# SMAC-2530.net
KiCad netlist of a schematic drawn in EAGLE
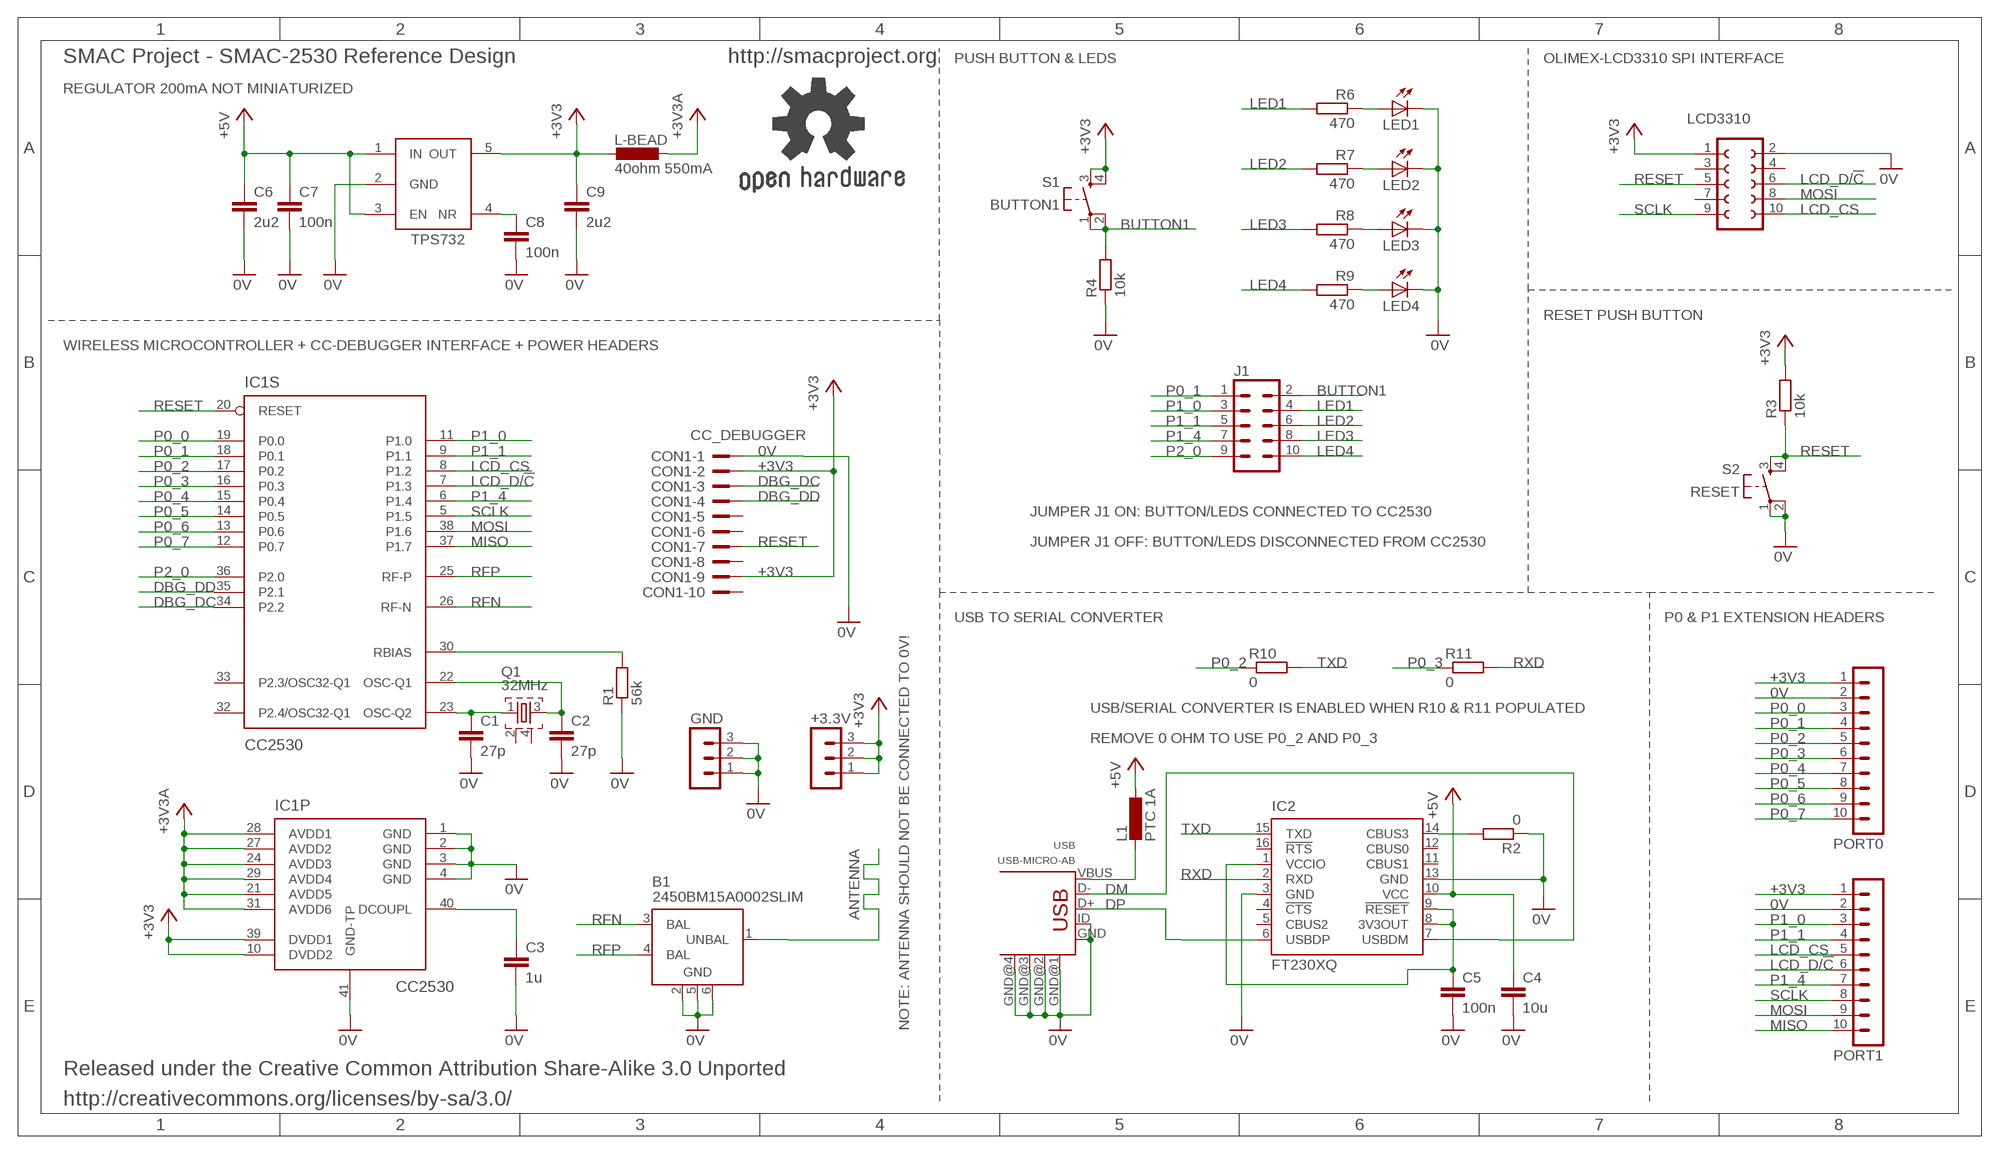
[diagram p0: schematic, sheet 1]

(export (version "E")
  (design (tool "Eeschema 10.0.6"))
  (components
    (comp (ref "+3.3V")
      (value "MA03-1")
      (footprint "eagle-import:MA03-1")
      (libsource (lib "eagle-import") (part "MA03-1"))
    )
    (comp (ref "B1")
      (value "2450BM15A0002SLIM")
      (footprint "eagle-import:2450BM15A0002-SLIM")
      (libsource (lib "eagle-import") (part "2450BM15A0002SLIM"))
    )
    (comp (ref "C1")
      (value "27p")
      (footprint "eagle-import:C0603K")
      (libsource (lib "eagle-import") (part "C-EUC0603K"))
    )
    (comp (ref "C2")
      (value "27p")
      (footprint "eagle-import:C0603K")
      (libsource (lib "eagle-import") (part "C-EUC0603K"))
    )
    (comp (ref "C3")
      (value "1u")
      (footprint "eagle-import:C0603K")
      (libsource (lib "eagle-import") (part "C-EUC0603K"))
    )
    (comp (ref "C4")
      (value "10u")
      (footprint "eagle-import:C0603K")
      (libsource (lib "eagle-import") (part "C-EUC0603K"))
    )
    (comp (ref "C5")
      (value "100n")
      (footprint "eagle-import:C0603K")
      (libsource (lib "eagle-import") (part "C-EUC0603K"))
    )
    (comp (ref "C6")
      (value "2u2")
      (footprint "eagle-import:C0603K")
      (libsource (lib "eagle-import") (part "C-EUC0603K"))
    )
    (comp (ref "C7")
      (value "100n")
      (footprint "eagle-import:C0603K")
      (libsource (lib "eagle-import") (part "C-EUC0603K"))
    )
    (comp (ref "C8")
      (value "100n")
      (footprint "eagle-import:C0603K")
      (libsource (lib "eagle-import") (part "C-EUC0603K"))
    )
    (comp (ref "C9")
      (value "2u2")
      (footprint "eagle-import:C0603K")
      (libsource (lib "eagle-import") (part "C-EUC0603K"))
    )
    (comp (ref "CON1")
      (value "CC_DEBUGGER")
      (footprint "eagle-import:PAK100_2500-10")
      (fields (field (name "MF") "3M") (field (name "MPN") "2510-6002UB"))
      (libsource (lib "eagle-import") (part "2510-"))
    )
    (comp (ref "GND")
      (value "MA03-1")
      (footprint "eagle-import:MA03-1")
      (libsource (lib "eagle-import") (part "MA03-1"))
    )
    (comp (ref "GOLD_ORB_SM1")
      (value "OSHWLOGO_GOLD_ORB_SM")
      (footprint "eagle-import:OSHW2")
      (libsource (lib "eagle-import") (part "OSHWLOGO_GOLD_ORB_SM"))
    )
    (comp (ref "IC1")
      (value "CC2530")
      (footprint "eagle-import:QFN50P600X600X100-41N")
      (libsource (lib "eagle-import") (part "CC2530"))
    )
    (comp (ref "IC2")
      (value "FT230XQ")
      (footprint "eagle-import:QFN16")
      (libsource (lib "eagle-import") (part "FT230XQ"))
    )
    (comp (ref "IC3")
      (value "TPS732XX")
      (footprint "eagle-import:SOT23")
      (libsource (lib "eagle-import") (part "TPS732XX"))
    )
    (comp (ref "J1")
      (value "MA05-2")
      (footprint "eagle-import:MA05-2")
      (libsource (lib "eagle-import") (part "MA05-2"))
    )
    (comp (ref "L-BEAD")
      (value "40ohm 550mA")
      (footprint "eagle-import:L0603K")
      (libsource (lib "eagle-import") (part "L-EUL0603K"))
    )
    (comp (ref "L1")
      (value "PTC 1A")
      (footprint "eagle-import:L0603K")
      (libsource (lib "eagle-import") (part "L-EUL0603K"))
    )
    (comp (ref "LCD3310")
      (value "FE05-2")
      (footprint "eagle-import:FE05-2")
      (libsource (lib "eagle-import") (part "FE05-2"))
    )
    (comp (ref "LED1")
      (value "LEDCHIP-LED0805")
      (footprint "eagle-import:CHIP-LED0805")
      (libsource (lib "eagle-import") (part "LEDCHIP-LED0805"))
    )
    (comp (ref "LED2")
      (value "LEDCHIP-LED0805")
      (footprint "eagle-import:CHIP-LED0805")
      (libsource (lib "eagle-import") (part "LEDCHIP-LED0805"))
    )
    (comp (ref "LED3")
      (value "LEDCHIP-LED0805")
      (footprint "eagle-import:CHIP-LED0805")
      (libsource (lib "eagle-import") (part "LEDCHIP-LED0805"))
    )
    (comp (ref "LED4")
      (value "LEDCHIP-LED0805")
      (footprint "eagle-import:CHIP-LED0805")
      (libsource (lib "eagle-import") (part "LEDCHIP-LED0805"))
    )
    (comp (ref "PORT0")
      (value "MA10-1")
      (footprint "eagle-import:MA10-1")
      (libsource (lib "eagle-import") (part "MA10-1"))
    )
    (comp (ref "PORT1")
      (value "MA10-1")
      (footprint "eagle-import:MA10-1")
      (libsource (lib "eagle-import") (part "MA10-1"))
    )
    (comp (ref "Q1")
      (value "32MHz")
      (footprint "eagle-import:FA-128")
      (libsource (lib "eagle-import") (part "FA-128"))
    )
    (comp (ref "R1")
      (value "56k")
      (footprint "eagle-import:R0603K")
      (libsource (lib "eagle-import") (part "R-EU_R0603K"))
    )
    (comp (ref "R2")
      (value "0")
      (footprint "eagle-import:R0603K")
      (libsource (lib "eagle-import") (part "R-EU_R0603K"))
    )
    (comp (ref "R3")
      (value "10k")
      (footprint "eagle-import:R0603K")
      (libsource (lib "eagle-import") (part "R-EU_R0603K"))
    )
    (comp (ref "R4")
      (value "10k")
      (footprint "eagle-import:R0603K")
      (libsource (lib "eagle-import") (part "R-EU_R0603K"))
    )
    (comp (ref "R6")
      (value "470")
      (footprint "eagle-import:R0603K")
      (libsource (lib "eagle-import") (part "R-EU_R0603K"))
    )
    (comp (ref "R7")
      (value "470")
      (footprint "eagle-import:R0603K")
      (libsource (lib "eagle-import") (part "R-EU_R0603K"))
    )
    (comp (ref "R8")
      (value "470")
      (footprint "eagle-import:R0603K")
      (libsource (lib "eagle-import") (part "R-EU_R0603K"))
    )
    (comp (ref "R9")
      (value "470")
      (footprint "eagle-import:R0603K")
      (libsource (lib "eagle-import") (part "R-EU_R0603K"))
    )
    (comp (ref "R10")
      (value "0")
      (footprint "eagle-import:R0603K")
      (libsource (lib "eagle-import") (part "R-EU_R0603K"))
    )
    (comp (ref "R11")
      (value "0")
      (footprint "eagle-import:R0603K")
      (libsource (lib "eagle-import") (part "R-EU_R0603K"))
    )
    (comp (ref "S1")
      (value "BUTTON1")
      (footprint "eagle-import:ALCOSWITCH-SMD")
      (libsource (lib "eagle-import") (part "ALCOSWITCH-SMD"))
    )
    (comp (ref "S2")
      (value "RESET")
      (footprint "eagle-import:ALCOSWITCH-SMD")
      (libsource (lib "eagle-import") (part "ALCOSWITCH-SMD"))
    )
    (comp (ref "USB")
      (value "USB-MICRO-AB")
      (footprint "eagle-import:USB-UAB-S1")
      (libsource (lib "eagle-import") (part "USB-OTG_SHIELD"))
    )
  )
  (nets
    (net (code "1") (name "+3V3") (class "Default")
      (node (ref "+3.3V") (pin "1") (pinfunction "1_1") (pintype "passive"))
      (node (ref "+3.3V") (pin "2") (pinfunction "2_2") (pintype "passive"))
      (node (ref "+3.3V") (pin "3") (pinfunction "3_3") (pintype "passive"))
      (node (ref "C9") (pin "1") (pinfunction "1_1") (pintype "passive"))
      (node (ref "CON1") (pin "2") (pinfunction "KL_2") (pintype "passive"))
      (node (ref "CON1") (pin "9") (pinfunction "KL_9") (pintype "passive"))
      (node (ref "IC1") (pin "10") (pinfunction "DVDD2_10") (pintype "power_in"))
      (node (ref "IC1") (pin "39") (pinfunction "DVDD1_39") (pintype "power_in"))
      (node (ref "IC3") (pin "5") (pinfunction "OUT_5") (pintype "bidirectional"))
      (node (ref "L-BEAD") (pin "1") (pinfunction "1_1") (pintype "passive"))
      (node (ref "LCD3310") (pin "1") (pinfunction "1_1") (pintype "passive"))
      (node (ref "PORT0") (pin "1") (pinfunction "1_1") (pintype "passive"))
      (node (ref "PORT1") (pin "1") (pinfunction "1_1") (pintype "passive"))
      (node (ref "R3") (pin "2") (pinfunction "2_2") (pintype "passive"))
      (node (ref "S1") (pin "3") (pinfunction "S_3") (pintype "passive"))
      (node (ref "S1") (pin "4") (pinfunction "S1_4") (pintype "passive"))
    )
    (net (code "2") (name "+3V3A") (class "Default")
      (node (ref "IC1") (pin "21") (pinfunction "AVDD5_21") (pintype "power_in"))
      (node (ref "IC1") (pin "24") (pinfunction "AVDD3_24") (pintype "power_in"))
      (node (ref "IC1") (pin "27") (pinfunction "AVDD2_27") (pintype "power_in"))
      (node (ref "IC1") (pin "28") (pinfunction "AVDD1_28") (pintype "power_in"))
      (node (ref "IC1") (pin "29") (pinfunction "AVDD4_29") (pintype "power_in"))
      (node (ref "IC1") (pin "31") (pinfunction "AVDD6_31") (pintype "power_in"))
      (node (ref "L-BEAD") (pin "2") (pinfunction "2_2") (pintype "passive"))
    )
    (net (code "3") (name "+5V") (class "Default")
      (node (ref "C4") (pin "1") (pinfunction "1_1") (pintype "passive"))
      (node (ref "C6") (pin "1") (pinfunction "1_1") (pintype "passive"))
      (node (ref "C7") (pin "1") (pinfunction "1_1") (pintype "passive"))
      (node (ref "IC2") (pin "10") (pinfunction "VCC_10") (pintype "power_in"))
      (node (ref "IC3") (pin "1") (pinfunction "IN_1") (pintype "bidirectional"))
      (node (ref "IC3") (pin "3") (pinfunction "EN_3") (pintype "bidirectional"))
      (node (ref "L1") (pin "1") (pinfunction "1_1") (pintype "passive"))
    )
    (net (code "4") (name "/BUTTON1") (class "Default")
      (node (ref "J1") (pin "2") (pinfunction "2_2") (pintype "passive"))
      (node (ref "R4") (pin "2") (pinfunction "2_2") (pintype "passive"))
      (node (ref "S1") (pin "1") (pinfunction "P_1") (pintype "passive"))
      (node (ref "S1") (pin "2") (pinfunction "P1_2") (pintype "passive"))
    )
    (net (code "5") (name "/DBG_DC") (class "Default")
      (node (ref "CON1") (pin "3") (pinfunction "KL_3") (pintype "passive"))
      (node (ref "IC1") (pin "34") (pinfunction "P2.2_34") (pintype "bidirectional"))
    )
    (net (code "6") (name "/DBG_DD") (class "Default")
      (node (ref "CON1") (pin "4") (pinfunction "KL_4") (pintype "passive"))
      (node (ref "IC1") (pin "35") (pinfunction "P2.1_35") (pintype "bidirectional"))
    )
    (net (code "7") (name "/DM") (class "Default")
      (node (ref "IC2") (pin "7") (pinfunction "USBDM_7") (pintype "input"))
      (node (ref "USB") (pin "D-") (pinfunction "D-_D-") (pintype "bidirectional"))
    )
    (net (code "8") (name "/DP") (class "Default")
      (node (ref "IC2") (pin "6") (pinfunction "USBDP_6") (pintype "input"))
      (node (ref "USB") (pin "D+") (pinfunction "D+_D+") (pintype "bidirectional"))
    )
    (net (code "9") (name "/LCD_CS") (class "Default")
      (node (ref "IC1") (pin "8") (pinfunction "P1.2_8") (pintype "bidirectional"))
      (node (ref "LCD3310") (pin "10") (pinfunction "10_10") (pintype "passive"))
      (node (ref "PORT1") (pin "5") (pinfunction "5_5") (pintype "passive"))
    )
    (net (code "10") (name "/LCD_D{slash}~{C}") (class "Default")
      (node (ref "IC1") (pin "7") (pinfunction "P1.3_7") (pintype "bidirectional"))
      (node (ref "LCD3310") (pin "6") (pinfunction "6_6") (pintype "passive"))
      (node (ref "PORT1") (pin "6") (pinfunction "6_6") (pintype "passive"))
    )
    (net (code "11") (name "/LED1") (class "Default")
      (node (ref "J1") (pin "4") (pinfunction "4_4") (pintype "passive"))
      (node (ref "R6") (pin "2") (pinfunction "2_2") (pintype "passive"))
    )
    (net (code "12") (name "/LED2") (class "Default")
      (node (ref "J1") (pin "6") (pinfunction "6_6") (pintype "passive"))
      (node (ref "R7") (pin "2") (pinfunction "2_2") (pintype "passive"))
    )
    (net (code "13") (name "/LED3") (class "Default")
      (node (ref "J1") (pin "8") (pinfunction "8_8") (pintype "passive"))
      (node (ref "R8") (pin "2") (pinfunction "2_2") (pintype "passive"))
    )
    (net (code "14") (name "/LED4") (class "Default")
      (node (ref "J1") (pin "10") (pinfunction "10_10") (pintype "passive"))
      (node (ref "R9") (pin "2") (pinfunction "2_2") (pintype "passive"))
    )
    (net (code "15") (name "/MISO") (class "Default")
      (node (ref "IC1") (pin "37") (pinfunction "P1.7_37") (pintype "bidirectional"))
      (node (ref "PORT1") (pin "10") (pinfunction "10_10") (pintype "passive"))
    )
    (net (code "16") (name "/MOSI") (class "Default")
      (node (ref "IC1") (pin "38") (pinfunction "P1.6_38") (pintype "bidirectional"))
      (node (ref "LCD3310") (pin "8") (pinfunction "8_8") (pintype "passive"))
      (node (ref "PORT1") (pin "9") (pinfunction "9_9") (pintype "passive"))
    )
    (net (code "17") (name "/P0_0") (class "Default")
      (node (ref "IC1") (pin "19") (pinfunction "P0.0_19") (pintype "bidirectional"))
      (node (ref "PORT0") (pin "3") (pinfunction "3_3") (pintype "passive"))
    )
    (net (code "18") (name "/P0_1") (class "Default")
      (node (ref "IC1") (pin "18") (pinfunction "P0.1_18") (pintype "bidirectional"))
      (node (ref "J1") (pin "1") (pinfunction "1_1") (pintype "passive"))
      (node (ref "PORT0") (pin "4") (pinfunction "4_4") (pintype "passive"))
    )
    (net (code "19") (name "/P0_2") (class "Default")
      (node (ref "IC1") (pin "17") (pinfunction "P0.2_17") (pintype "bidirectional"))
      (node (ref "PORT0") (pin "5") (pinfunction "5_5") (pintype "passive"))
      (node (ref "R10") (pin "1") (pinfunction "1_1") (pintype "passive"))
    )
    (net (code "20") (name "/P0_3") (class "Default")
      (node (ref "IC1") (pin "16") (pinfunction "P0.3_16") (pintype "bidirectional"))
      (node (ref "PORT0") (pin "6") (pinfunction "6_6") (pintype "passive"))
      (node (ref "R11") (pin "1") (pinfunction "1_1") (pintype "passive"))
    )
    (net (code "21") (name "/P0_4") (class "Default")
      (node (ref "IC1") (pin "15") (pinfunction "P0.4_15") (pintype "bidirectional"))
      (node (ref "PORT0") (pin "7") (pinfunction "7_7") (pintype "passive"))
    )
    (net (code "22") (name "/P0_5") (class "Default")
      (node (ref "IC1") (pin "14") (pinfunction "P0.5_14") (pintype "bidirectional"))
      (node (ref "PORT0") (pin "8") (pinfunction "8_8") (pintype "passive"))
    )
    (net (code "23") (name "/P0_6") (class "Default")
      (node (ref "IC1") (pin "13") (pinfunction "P0.6_13") (pintype "bidirectional"))
      (node (ref "PORT0") (pin "9") (pinfunction "9_9") (pintype "passive"))
    )
    (net (code "24") (name "/P0_7") (class "Default")
      (node (ref "IC1") (pin "12") (pinfunction "P0.7_12") (pintype "bidirectional"))
      (node (ref "PORT0") (pin "10") (pinfunction "10_10") (pintype "passive"))
    )
    (net (code "25") (name "/P1_0") (class "Default")
      (node (ref "IC1") (pin "11") (pinfunction "P1.0_11") (pintype "bidirectional"))
      (node (ref "J1") (pin "3") (pinfunction "3_3") (pintype "passive"))
      (node (ref "PORT1") (pin "3") (pinfunction "3_3") (pintype "passive"))
    )
    (net (code "26") (name "/P1_1") (class "Default")
      (node (ref "IC1") (pin "9") (pinfunction "P1.1_9") (pintype "bidirectional"))
      (node (ref "J1") (pin "5") (pinfunction "5_5") (pintype "passive"))
      (node (ref "PORT1") (pin "4") (pinfunction "4_4") (pintype "passive"))
    )
    (net (code "27") (name "/P1_4") (class "Default")
      (node (ref "IC1") (pin "6") (pinfunction "P1.4_6") (pintype "bidirectional"))
      (node (ref "J1") (pin "7") (pinfunction "7_7") (pintype "passive"))
      (node (ref "PORT1") (pin "7") (pinfunction "7_7") (pintype "passive"))
    )
    (net (code "28") (name "/P2_0") (class "Default")
      (node (ref "IC1") (pin "36") (pinfunction "P2.0_36") (pintype "bidirectional"))
      (node (ref "J1") (pin "9") (pinfunction "9_9") (pintype "passive"))
    )
    (net (code "29") (name "/RESET") (class "Default")
      (node (ref "CON1") (pin "7") (pinfunction "KL_7") (pintype "passive"))
      (node (ref "IC1") (pin "20") (pinfunction "RESET_20") (pintype "input"))
      (node (ref "LCD3310") (pin "5") (pinfunction "5_5") (pintype "passive"))
      (node (ref "R3") (pin "1") (pinfunction "1_1") (pintype "passive"))
      (node (ref "S2") (pin "3") (pinfunction "S_3") (pintype "passive"))
      (node (ref "S2") (pin "4") (pinfunction "S1_4") (pintype "passive"))
    )
    (net (code "30") (name "/RFN") (class "Default")
      (node (ref "B1") (pin "3") (pinfunction "BAL_3") (pintype "passive"))
      (node (ref "IC1") (pin "26") (pinfunction "RF-N_26") (pintype "bidirectional"))
    )
    (net (code "31") (name "/RFP") (class "Default")
      (node (ref "B1") (pin "4") (pinfunction "BAL_4") (pintype "passive"))
      (node (ref "IC1") (pin "25") (pinfunction "RF-P_25") (pintype "bidirectional"))
    )
    (net (code "32") (name "/RXD") (class "Default")
      (node (ref "IC2") (pin "2") (pinfunction "RXD_2") (pintype "input"))
      (node (ref "R11") (pin "2") (pinfunction "2_2") (pintype "passive"))
    )
    (net (code "33") (name "/SCLK") (class "Default")
      (node (ref "IC1") (pin "5") (pinfunction "P1.5_5") (pintype "bidirectional"))
      (node (ref "LCD3310") (pin "9") (pinfunction "9_9") (pintype "passive"))
      (node (ref "PORT1") (pin "8") (pinfunction "8_8") (pintype "passive"))
    )
    (net (code "34") (name "/TXD") (class "Default")
      (node (ref "IC2") (pin "15") (pinfunction "TXD_15") (pintype "output"))
      (node (ref "R10") (pin "2") (pinfunction "2_2") (pintype "passive"))
    )
    (net (code "35") (name "0V") (class "Default")
      (node (ref "B1") (pin "1") (pinfunction "UNBAL_1") (pintype "passive"))
      (node (ref "B1") (pin "2") (pinfunction "GND_2") (pintype "passive"))
      (node (ref "B1") (pin "5") (pinfunction "GND_5") (pintype "passive"))
      (node (ref "B1") (pin "6") (pinfunction "GND_6") (pintype "passive"))
      (node (ref "C1") (pin "2") (pinfunction "2_2") (pintype "passive"))
      (node (ref "C2") (pin "2") (pinfunction "2_2") (pintype "passive"))
      (node (ref "C3") (pin "2") (pinfunction "2_2") (pintype "passive"))
      (node (ref "C4") (pin "2") (pinfunction "2_2") (pintype "passive"))
      (node (ref "C5") (pin "2") (pinfunction "2_2") (pintype "passive"))
      (node (ref "C6") (pin "2") (pinfunction "2_2") (pintype "passive"))
      (node (ref "C7") (pin "2") (pinfunction "2_2") (pintype "passive"))
      (node (ref "C8") (pin "2") (pinfunction "2_2") (pintype "passive"))
      (node (ref "C9") (pin "2") (pinfunction "2_2") (pintype "passive"))
      (node (ref "CON1") (pin "1") (pinfunction "KL_1") (pintype "passive"))
      (node (ref "GND") (pin "1") (pinfunction "1_1") (pintype "passive"))
      (node (ref "GND") (pin "2") (pinfunction "2_2") (pintype "passive"))
      (node (ref "GND") (pin "3") (pinfunction "3_3") (pintype "passive"))
      (node (ref "IC1") (pin "1") (pinfunction "GND_1") (pintype "power_in"))
      (node (ref "IC1") (pin "2") (pinfunction "GND_2") (pintype "power_in"))
      (node (ref "IC1") (pin "3") (pinfunction "GND_3") (pintype "power_in"))
      (node (ref "IC1") (pin "4") (pinfunction "GND_4") (pintype "power_in"))
      (node (ref "IC1") (pin "41") (pinfunction "GND-TP_41") (pintype "power_in"))
      (node (ref "IC2") (pin "13") (pinfunction "GND_13") (pintype "power_in"))
      (node (ref "IC2") (pin "3") (pinfunction "GND_3") (pintype "power_in"))
      (node (ref "IC3") (pin "2") (pinfunction "GND_2") (pintype "bidirectional"))
      (node (ref "LCD3310") (pin "2") (pinfunction "2_2") (pintype "passive"))
      (node (ref "LED1") (pin "C") (pinfunction "C_C") (pintype "passive"))
      (node (ref "LED2") (pin "C") (pinfunction "C_C") (pintype "passive"))
      (node (ref "LED3") (pin "C") (pinfunction "C_C") (pintype "passive"))
      (node (ref "LED4") (pin "C") (pinfunction "C_C") (pintype "passive"))
      (node (ref "PORT0") (pin "2") (pinfunction "2_2") (pintype "passive"))
      (node (ref "PORT1") (pin "2") (pinfunction "2_2") (pintype "passive"))
      (node (ref "R1") (pin "1") (pinfunction "1_1") (pintype "passive"))
      (node (ref "R2") (pin "1") (pinfunction "1_1") (pintype "passive"))
      (node (ref "R4") (pin "1") (pinfunction "1_1") (pintype "passive"))
      (node (ref "S2") (pin "1") (pinfunction "P_1") (pintype "passive"))
      (node (ref "S2") (pin "2") (pinfunction "P1_2") (pintype "passive"))
      (node (ref "USB") (pin "GND") (pinfunction "GND_GND") (pintype "power_in"))
      (node (ref "USB") (pin "GND@1") (pinfunction "GND_GND@1") (pintype "power_in"))
      (node (ref "USB") (pin "GND@2") (pinfunction "GND_GND@2") (pintype "power_in"))
      (node (ref "USB") (pin "GND@3") (pinfunction "GND_GND@3") (pintype "power_in"))
      (node (ref "USB") (pin "GND@4") (pinfunction "GND_GND@4") (pintype "power_in"))
      (node (ref "USB") (pin "ID") (pinfunction "ID_ID") (pintype "bidirectional"))
    )
    (net (code "36") (name "Net-(IC1A-DCOUPL)") (class "Default")
      (node (ref "C3") (pin "1") (pinfunction "1_1") (pintype "passive"))
      (node (ref "IC1") (pin "40") (pinfunction "DCOUPL_40") (pintype "power_in"))
    )
    (net (code "37") (name "Net-(IC1B-OSC-Q1)") (class "Default")
      (node (ref "C2") (pin "1") (pinfunction "1_1") (pintype "passive"))
      (node (ref "IC1") (pin "22") (pinfunction "OSC-Q1_22") (pintype "bidirectional"))
      (node (ref "Q1") (pin "3") (pinfunction "3_3") (pintype "passive"))
    )
    (net (code "38") (name "Net-(IC1B-OSC-Q2)") (class "Default")
      (node (ref "C1") (pin "1") (pinfunction "1_1") (pintype "passive"))
      (node (ref "IC1") (pin "23") (pinfunction "OSC-Q2_23") (pintype "bidirectional"))
      (node (ref "Q1") (pin "1") (pinfunction "1_1") (pintype "passive"))
    )
    (net (code "39") (name "Net-(IC1B-RBIAS)") (class "Default")
      (node (ref "IC1") (pin "30") (pinfunction "RBIAS_30") (pintype "bidirectional"))
      (node (ref "R1") (pin "2") (pinfunction "2_2") (pintype "passive"))
    )
    (net (code "40") (name "Net-(IC2-3V3OUT)") (class "Default")
      (node (ref "C5") (pin "1") (pinfunction "1_1") (pintype "passive"))
      (node (ref "IC2") (pin "1") (pinfunction "VCCIO_1") (pintype "power_in"))
      (node (ref "IC2") (pin "8") (pinfunction "3V3OUT_8") (pintype "output"))
      (node (ref "IC2") (pin "9") (pinfunction "~{RESET}_9") (pintype "input"))
    )
    (net (code "41") (name "Net-(IC2-CBUS3)") (class "Default")
      (node (ref "IC2") (pin "14") (pinfunction "CBUS3_14") (pintype "bidirectional"))
      (node (ref "R2") (pin "2") (pinfunction "2_2") (pintype "passive"))
    )
    (net (code "42") (name "Net-(IC3-NR)") (class "Default")
      (node (ref "C8") (pin "1") (pinfunction "1_1") (pintype "passive"))
      (node (ref "IC3") (pin "4") (pinfunction "NR_4") (pintype "bidirectional"))
    )
    (net (code "43") (name "Net-(L1-Pad2)") (class "Default")
      (node (ref "L1") (pin "2") (pinfunction "2_2") (pintype "passive"))
      (node (ref "USB") (pin "VBUS") (pinfunction "VBUS_VBUS") (pintype "power_in"))
    )
    (net (code "44") (name "Net-(LED1-PadA)") (class "Default")
      (node (ref "LED1") (pin "A") (pinfunction "A_A") (pintype "passive"))
      (node (ref "R6") (pin "1") (pinfunction "1_1") (pintype "passive"))
    )
    (net (code "45") (name "Net-(LED2-PadA)") (class "Default")
      (node (ref "LED2") (pin "A") (pinfunction "A_A") (pintype "passive"))
      (node (ref "R7") (pin "1") (pinfunction "1_1") (pintype "passive"))
    )
    (net (code "46") (name "Net-(LED3-PadA)") (class "Default")
      (node (ref "LED3") (pin "A") (pinfunction "A_A") (pintype "passive"))
      (node (ref "R8") (pin "1") (pinfunction "1_1") (pintype "passive"))
    )
    (net (code "47") (name "Net-(LED4-PadA)") (class "Default")
      (node (ref "LED4") (pin "A") (pinfunction "A_A") (pintype "passive"))
      (node (ref "R9") (pin "1") (pinfunction "1_1") (pintype "passive"))
    )
    (net (code "48") (name "unconnected-(CON1B-KL-Pad10)") (class "Default")
      (node (ref "CON1") (pin "10") (pinfunction "KL_10") (pintype "passive"))
    )
    (net (code "49") (name "unconnected-(CON1F-KL-Pad5)") (class "Default")
      (node (ref "CON1") (pin "5") (pinfunction "KL_5") (pintype "passive"))
    )
    (net (code "50") (name "unconnected-(CON1G-KL-Pad6)") (class "Default")
      (node (ref "CON1") (pin "6") (pinfunction "KL_6") (pintype "passive"))
    )
    (net (code "51") (name "unconnected-(CON1I-KL-Pad8)") (class "Default")
      (node (ref "CON1") (pin "8") (pinfunction "KL_8") (pintype "passive"))
    )
    (net (code "52") (name "unconnected-(IC1B-P2.3{slash}OSC32-Q1-Pad33)") (class "Default")
      (node (ref "IC1") (pin "33") (pinfunction "P2.3/OSC32-Q1_33") (pintype "bidirectional"))
    )
    (net (code "53") (name "unconnected-(IC1B-P2.4{slash}OSC32-Q1-Pad32)") (class "Default")
      (node (ref "IC1") (pin "32") (pinfunction "P2.4/OSC32-Q1_32") (pintype "bidirectional"))
    )
    (net (code "54") (name "unconnected-(IC2-CBUS0-Pad12)") (class "Default")
      (node (ref "IC2") (pin "12") (pinfunction "CBUS0_12") (pintype "bidirectional"))
    )
    (net (code "55") (name "unconnected-(IC2-CBUS1-Pad11)") (class "Default")
      (node (ref "IC2") (pin "11") (pinfunction "CBUS1_11") (pintype "bidirectional"))
    )
    (net (code "56") (name "unconnected-(IC2-CBUS2-Pad5)") (class "Default")
      (node (ref "IC2") (pin "5") (pinfunction "CBUS2_5") (pintype "bidirectional"))
    )
    (net (code "57") (name "unconnected-(IC2-~{CTS}-Pad4)") (class "Default")
      (node (ref "IC2") (pin "4") (pinfunction "~{CTS}_4") (pintype "input"))
    )
    (net (code "58") (name "unconnected-(IC2-~{RTS}-Pad16)") (class "Default")
      (node (ref "IC2") (pin "16") (pinfunction "~{RTS}_16") (pintype "output"))
    )
    (net (code "59") (name "unconnected-(LCD3310-Pad3)") (class "Default")
      (node (ref "LCD3310") (pin "3") (pinfunction "3_3") (pintype "passive"))
    )
    (net (code "60") (name "unconnected-(LCD3310-Pad4)") (class "Default")
      (node (ref "LCD3310") (pin "4") (pinfunction "4_4") (pintype "passive"))
    )
    (net (code "61") (name "unconnected-(LCD3310-Pad7)") (class "Default")
      (node (ref "LCD3310") (pin "7") (pinfunction "7_7") (pintype "passive"))
    )
    (net (code "62") (name "unconnected-(Q1-Pad2)") (class "Default")
      (node (ref "Q1") (pin "2") (pinfunction "2_2") (pintype "passive"))
    )
    (net (code "63") (name "unconnected-(Q1-Pad4)") (class "Default")
      (node (ref "Q1") (pin "4") (pinfunction "4_4") (pintype "passive"))
    )
  )
)
